# GSM_INDICATION.net
KiCad netlist of a schematic drawn in Altium Designer
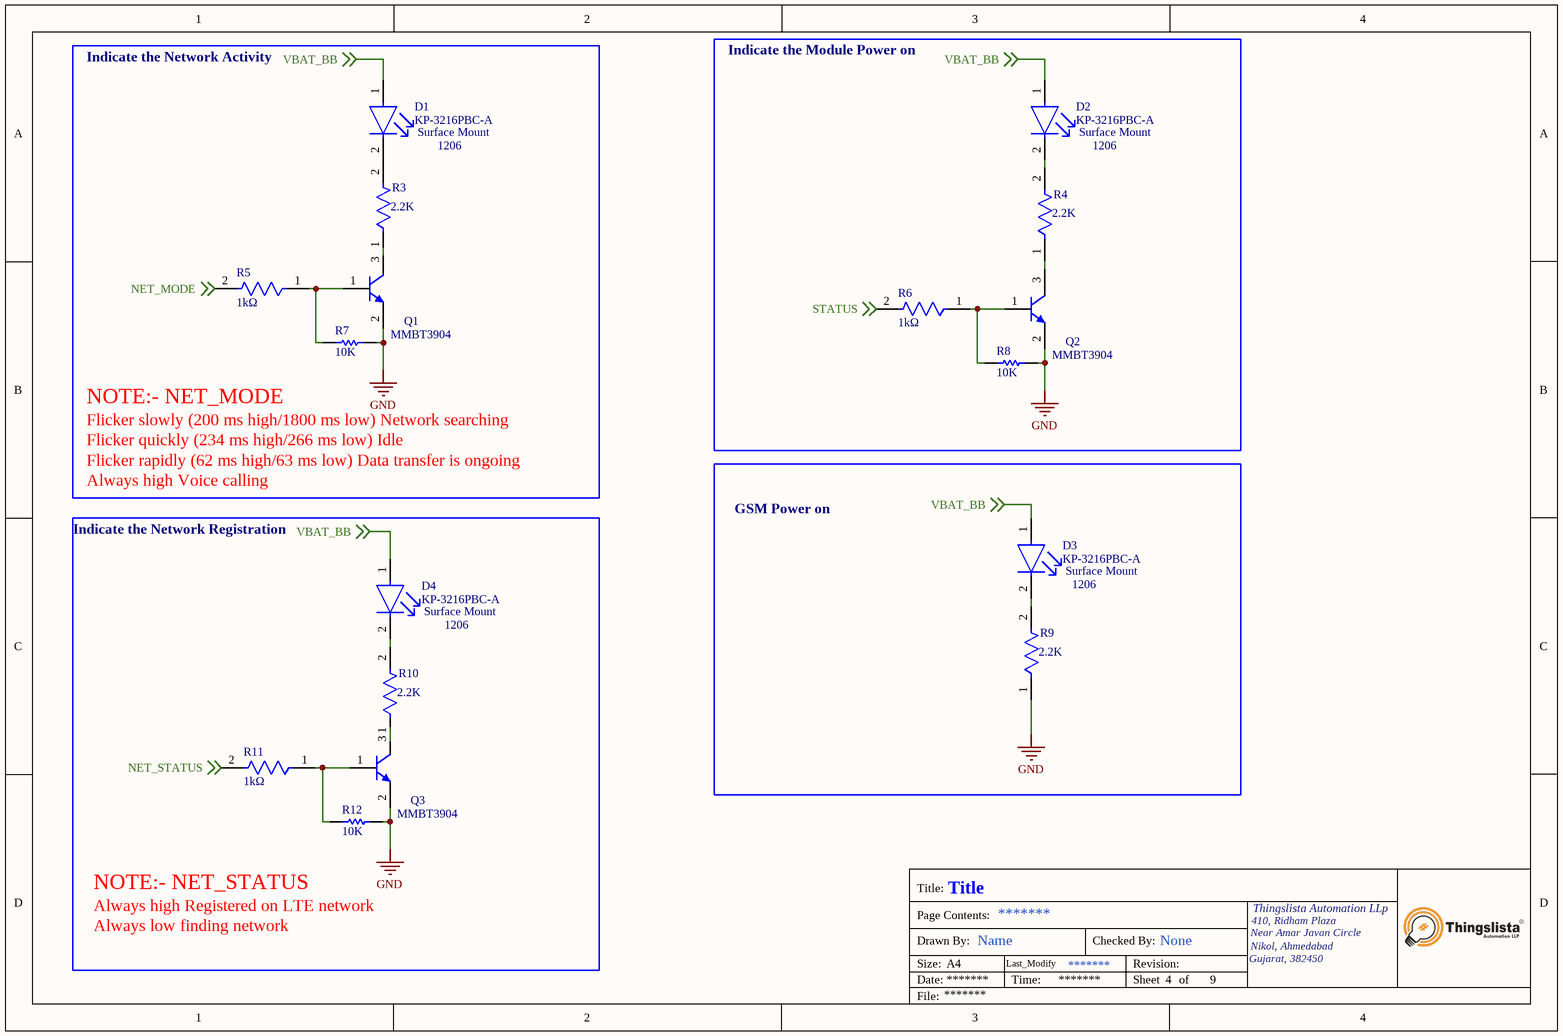
[diagram p0: GSM_INDICATION.SchDoc]

(export (version "E")
  (design (tool "Eeschema 10.0.6"))
  (components
    (comp (ref "D1")
      (value "KP-3216PBC-A")
      (footprint "FP-KP-3216PBC-A-MFG")
      (description "LED, Low Power, Blue, SMD, 1.6mm x 2mm, 20 mA, 3.2 V, 470 nm")
      (fields (field (name "SERIES") "1206") (field (name "MOUNT") "Surface Mount"))
      (libsource (lib "Altium Content Vault") (part "ab1c01a81903e929fc6c44469aada92"))
    )
    (comp (ref "D2")
      (value "KP-3216PBC-A")
      (footprint "FP-KP-3216PBC-A-MFG")
      (description "LED, Low Power, Blue, SMD, 1.6mm x 2mm, 20 mA, 3.2 V, 470 nm")
      (fields (field (name "SERIES") "1206") (field (name "MOUNT") "Surface Mount"))
      (libsource (lib "Altium Content Vault") (part "ab1c01a81903e929fc6c44469aada92"))
    )
    (comp (ref "D3")
      (value "KP-3216PBC-A")
      (footprint "FP-KP-3216PBC-A-MFG")
      (description "LED, Low Power, Blue, SMD, 1.6mm x 2mm, 20 mA, 3.2 V, 470 nm")
      (fields (field (name "SERIES") "1206") (field (name "MOUNT") "Surface Mount"))
      (libsource (lib "Altium Content Vault") (part "ab1c01a81903e929fc6c44469aada92"))
    )
    (comp (ref "D4")
      (value "KP-3216PBC-A")
      (footprint "FP-KP-3216PBC-A-MFG")
      (description "LED, Low Power, Blue, SMD, 1.6mm x 2mm, 20 mA, 3.2 V, 470 nm")
      (fields (field (name "SERIES") "1206") (field (name "MOUNT") "Surface Mount"))
      (libsource (lib "Altium Content Vault") (part "ab1c01a81903e929fc6c44469aada92"))
    )
    (comp (ref "Q1")
      (value "MMBT3904")
      (footprint "FAIR-SOT23-3_V")
      (description "NPN General Purpose Amplifier, 40 V, 0.2 A, -55 to 150 degC, 3-Pin SOT23, RoHS, Tape and Reel")
      (fields (field (name "TOLERANCE") "30ppm"))
      (libsource (lib "Altium Content Vault") (part "BJT-NPN-BEC-3"))
    )
    (comp (ref "Q2")
      (value "MMBT3904")
      (footprint "FAIR-SOT23-3_V")
      (description "NPN General Purpose Amplifier, 40 V, 0.2 A, -55 to 150 degC, 3-Pin SOT23, RoHS, Tape and Reel")
      (fields (field (name "TOLERANCE") "30ppm"))
      (libsource (lib "Altium Content Vault") (part "BJT-NPN-BEC-3"))
    )
    (comp (ref "Q3")
      (value "MMBT3904")
      (footprint "FAIR-SOT23-3_V")
      (description "NPN General Purpose Amplifier, 40 V, 0.2 A, -55 to 150 degC, 3-Pin SOT23, RoHS, Tape and Reel")
      (fields (field (name "TOLERANCE") "30ppm"))
      (libsource (lib "Altium Content Vault") (part "BJT-NPN-BEC-3"))
    )
    (comp (ref "R3")
      (value "CRCW08052K20FKEA")
      (footprint "FP-CRCW0805-e3-IPC_B")
      (description "RES Thick Film, 2.2kΩ, 1%, 0.125W, 100ppm/°C, 0805")
      (fields (field (name "RESISTANCE") "2.2K") (field (name "TOLERANCE") "1%"))
      (libsource (lib "Altium Content Vault") (part "1029c3af85768c4190bb7ad29bc67b5"))
    )
    (comp (ref "R4")
      (value "CRCW08052K20FKEA")
      (footprint "FP-CRCW0805-e3-IPC_B")
      (description "RES Thick Film, 2.2kΩ, 1%, 0.125W, 100ppm/°C, 0805")
      (fields (field (name "RESISTANCE") "2.2K") (field (name "TOLERANCE") "1%"))
      (libsource (lib "Altium Content Vault") (part "1029c3af85768c4190bb7ad29bc67b5"))
    )
    (comp (ref "R5")
      (value "CRG0805F1K0")
      (footprint "FP-CRG0805-IPC_A")
      (description "CRG0805F1K0 Thick Film Resistors - SMD 1K Ohm 1% 1/8W Res Thick Film 0805")
      (fields (field (name "TOLERANCE") "1%") (field (name "RESISTANCE") "1kΩ"))
      (libsource (lib "Altium Content Vault") (part "1029c3af85768c4190bb7ad29bc67b5"))
    )
    (comp (ref "R6")
      (value "CRG0805F1K0")
      (footprint "FP-CRG0805-IPC_A")
      (description "CRG0805F1K0 Thick Film Resistors - SMD 1K Ohm 1% 1/8W Res Thick Film 0805")
      (fields (field (name "TOLERANCE") "1%") (field (name "RESISTANCE") "1kΩ"))
      (libsource (lib "Altium Content Vault") (part "1029c3af85768c4190bb7ad29bc67b5"))
    )
    (comp (ref "R7")
      (value "10K")
      (footprint "RESC2013X60X35NL10T20")
      (description "Chip Resistor, 10 KOhm, +/- 1%, 0.125 W, -55 to 155 degC, 0805 (2012 Metric), RoHS, Tape and Reel")
      (fields (field (name "MANUFACTURER") "Yageo") (field (name "Comment") "RC0805FR-0710KL"))
      (libsource (lib "Altium Content Vault") (part "RES-2"))
    )
    (comp (ref "R8")
      (value "10K")
      (footprint "RESC2013X60X35NL10T20")
      (description "Chip Resistor, 10 KOhm, +/- 1%, 0.125 W, -55 to 155 degC, 0805 (2012 Metric), RoHS, Tape and Reel")
      (fields (field (name "MANUFACTURER") "Yageo") (field (name "Comment") "RC0805FR-0710KL"))
      (libsource (lib "Altium Content Vault") (part "RES-2"))
    )
    (comp (ref "R9")
      (value "CRCW08052K20FKEA")
      (footprint "FP-CRCW0805-e3-IPC_B")
      (description "RES Thick Film, 2.2kΩ, 1%, 0.125W, 100ppm/°C, 0805")
      (fields (field (name "RESISTANCE") "2.2K") (field (name "TOLERANCE") "1%"))
      (libsource (lib "Altium Content Vault") (part "1029c3af85768c4190bb7ad29bc67b5"))
    )
    (comp (ref "R10")
      (value "CRCW08052K20FKEA")
      (footprint "FP-CRCW0805-e3-IPC_B")
      (description "RES Thick Film, 2.2kΩ, 1%, 0.125W, 100ppm/°C, 0805")
      (fields (field (name "RESISTANCE") "2.2K") (field (name "TOLERANCE") "1%"))
      (libsource (lib "Altium Content Vault") (part "1029c3af85768c4190bb7ad29bc67b5"))
    )
    (comp (ref "R11")
      (value "CRG0805F1K0")
      (footprint "FP-CRG0805-IPC_A")
      (description "CRG0805F1K0 Thick Film Resistors - SMD 1K Ohm 1% 1/8W Res Thick Film 0805")
      (fields (field (name "TOLERANCE") "1%") (field (name "RESISTANCE") "1kΩ"))
      (libsource (lib "Altium Content Vault") (part "1029c3af85768c4190bb7ad29bc67b5"))
    )
    (comp (ref "R12")
      (value "10K")
      (footprint "RESC2013X60X35NL10T20")
      (description "Chip Resistor, 10 KOhm, +/- 1%, 0.125 W, -55 to 155 degC, 0805 (2012 Metric), RoHS, Tape and Reel")
      (fields (field (name "MANUFACTURER") "Yageo") (field (name "Comment") "RC0805FR-0710KL"))
      (libsource (lib "Altium Content Vault") (part "RES-2"))
    )
  )
  (nets
    (net (code "1") (name "GND") (class "Default")
      (node (ref "Q1") (pin "2") (pinfunction "E_2") (pintype "passive"))
      (node (ref "Q2") (pin "2") (pinfunction "E_2") (pintype "passive"))
      (node (ref "Q3") (pin "2") (pinfunction "E_2") (pintype "passive"))
      (node (ref "R12") (pin "1") (pinfunction "1_1") (pintype "passive"))
      (node (ref "R7") (pin "1") (pinfunction "1_1") (pintype "passive"))
      (node (ref "R8") (pin "1") (pinfunction "1_1") (pintype "passive"))
      (node (ref "R9") (pin "1") (pinfunction "1_1") (pintype "passive"))
    )
    (net (code "2") (name "NET_MODE") (class "Default")
      (node (ref "R5") (pin "2") (pinfunction "2_2") (pintype "passive"))
    )
    (net (code "3") (name "NET_STATUS") (class "Default")
      (node (ref "R11") (pin "2") (pinfunction "2_2") (pintype "passive"))
    )
    (net (code "4") (name "Net-(D1-C)") (class "Default")
      (node (ref "D1") (pin "2") (pinfunction "C_2") (pintype "passive"))
      (node (ref "R3") (pin "2") (pinfunction "2_2") (pintype "passive"))
    )
    (net (code "5") (name "Net-(D2-C)") (class "Default")
      (node (ref "D2") (pin "2") (pinfunction "C_2") (pintype "passive"))
      (node (ref "R4") (pin "2") (pinfunction "2_2") (pintype "passive"))
    )
    (net (code "6") (name "Net-(D3-C)") (class "Default")
      (node (ref "D3") (pin "2") (pinfunction "C_2") (pintype "passive"))
      (node (ref "R9") (pin "2") (pinfunction "2_2") (pintype "passive"))
    )
    (net (code "7") (name "Net-(D4-C)") (class "Default")
      (node (ref "D4") (pin "2") (pinfunction "C_2") (pintype "passive"))
      (node (ref "R10") (pin "2") (pinfunction "2_2") (pintype "passive"))
    )
    (net (code "8") (name "Net-(Q1-B)") (class "Default")
      (node (ref "Q1") (pin "1") (pinfunction "B_1") (pintype "passive"))
      (node (ref "R5") (pin "1") (pinfunction "1_1") (pintype "passive"))
      (node (ref "R7") (pin "2") (pinfunction "2_2") (pintype "passive"))
    )
    (net (code "9") (name "Net-(Q1-C)") (class "Default")
      (node (ref "Q1") (pin "3") (pinfunction "C_3") (pintype "passive"))
      (node (ref "R3") (pin "1") (pinfunction "1_1") (pintype "passive"))
    )
    (net (code "10") (name "Net-(Q2-B)") (class "Default")
      (node (ref "Q2") (pin "1") (pinfunction "B_1") (pintype "passive"))
      (node (ref "R6") (pin "1") (pinfunction "1_1") (pintype "passive"))
      (node (ref "R8") (pin "2") (pinfunction "2_2") (pintype "passive"))
    )
    (net (code "11") (name "Net-(Q2-C)") (class "Default")
      (node (ref "Q2") (pin "3") (pinfunction "C_3") (pintype "passive"))
      (node (ref "R4") (pin "1") (pinfunction "1_1") (pintype "passive"))
    )
    (net (code "12") (name "Net-(Q3-B)") (class "Default")
      (node (ref "Q3") (pin "1") (pinfunction "B_1") (pintype "passive"))
      (node (ref "R11") (pin "1") (pinfunction "1_1") (pintype "passive"))
      (node (ref "R12") (pin "2") (pinfunction "2_2") (pintype "passive"))
    )
    (net (code "13") (name "Net-(Q3-C)") (class "Default")
      (node (ref "Q3") (pin "3") (pinfunction "C_3") (pintype "passive"))
      (node (ref "R10") (pin "1") (pinfunction "1_1") (pintype "passive"))
    )
    (net (code "14") (name "STATUS") (class "Default")
      (node (ref "R6") (pin "2") (pinfunction "2_2") (pintype "passive"))
    )
    (net (code "15") (name "VBAT_BB") (class "Default")
      (node (ref "D1") (pin "1") (pinfunction "A_1") (pintype "passive"))
      (node (ref "D2") (pin "1") (pinfunction "A_1") (pintype "passive"))
      (node (ref "D3") (pin "1") (pinfunction "A_1") (pintype "passive"))
      (node (ref "D4") (pin "1") (pinfunction "A_1") (pintype "passive"))
    )
  )
)
